# module_RevC.net
KiCad netlist of a schematic drawn in EAGLE
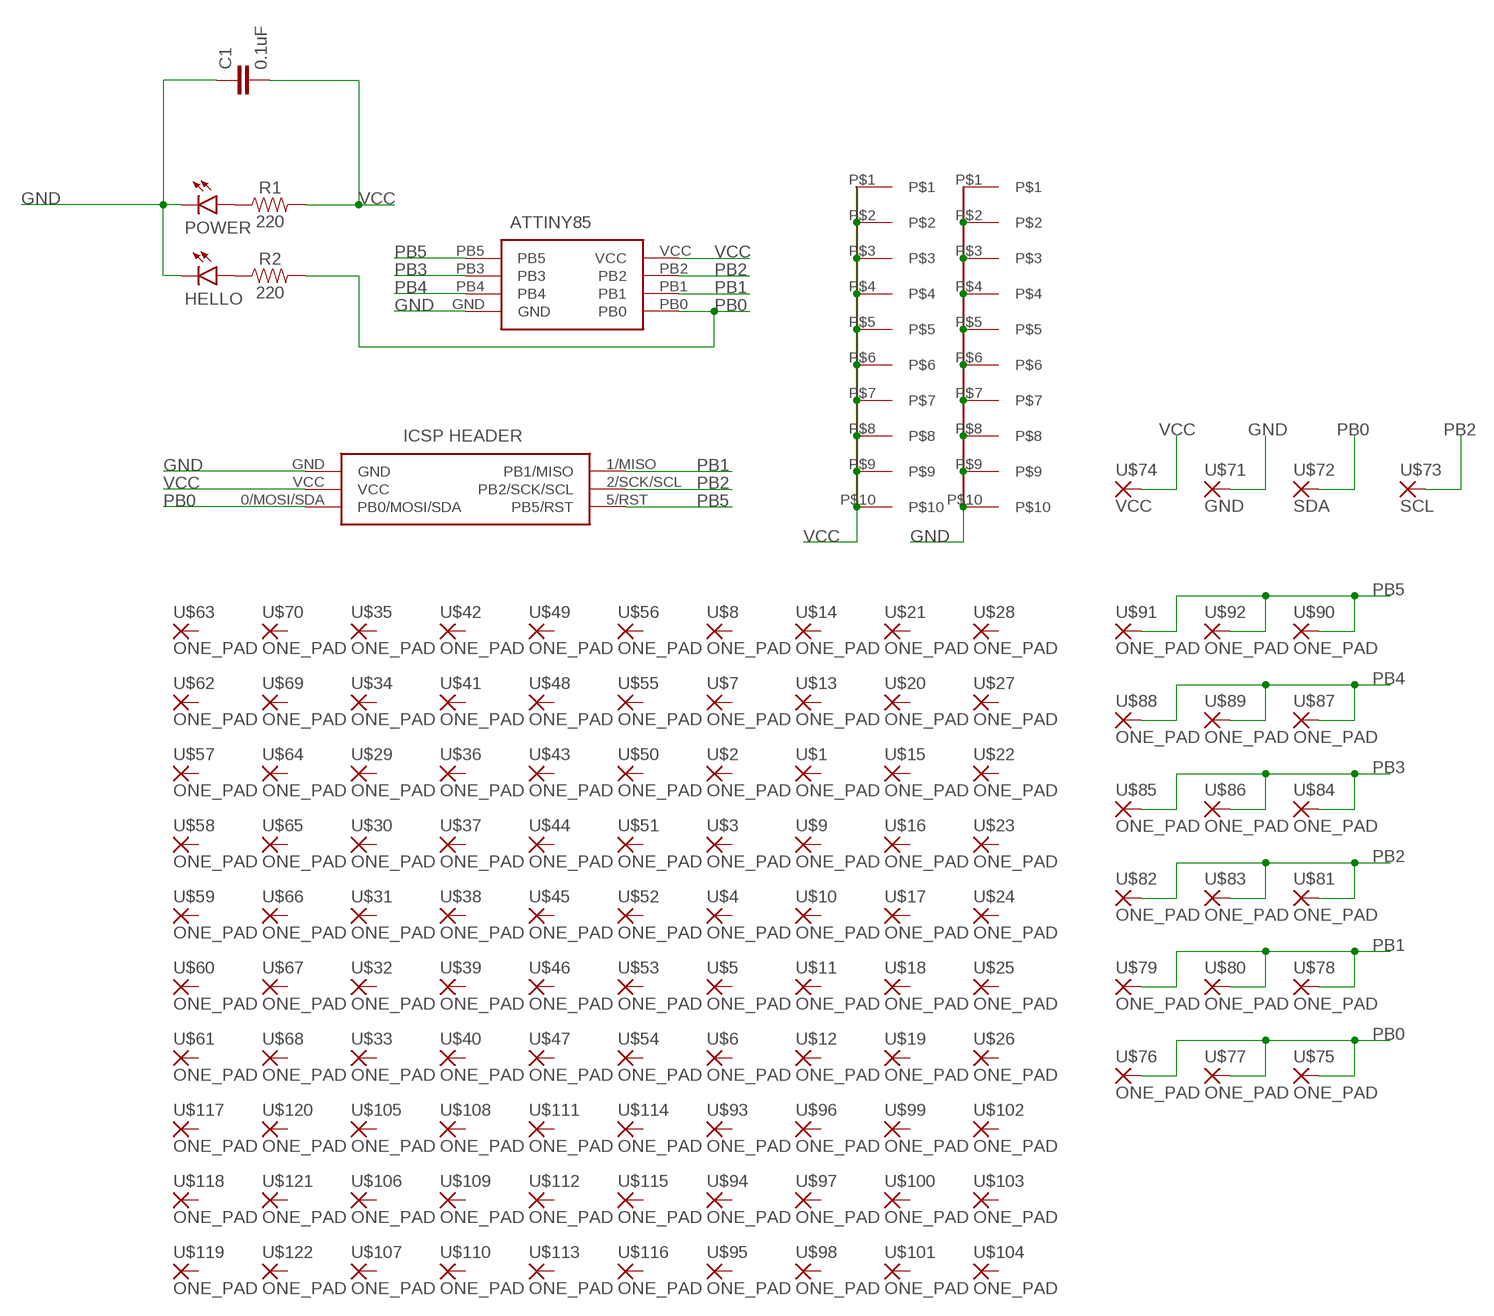
[diagram p0: schematic, sheet 1]

(export (version "E")
  (design (tool "Eeschema 10.0.6"))
  (components
    (comp (ref "C1")
      (value "0.1uF")
      (footprint "eagle-import:0603")
      (libsource (lib "eagle-import") (part "0.1UF-0603-25V-5%"))
    )
    (comp (ref "GND")
      (value "10X-PADS")
      (footprint "eagle-import:10X-PADS")
      (libsource (lib "eagle-import") (part "10X-PADS"))
    )
    (comp (ref "HELLO")
      (value "LED3MM")
      (footprint "eagle-import:LED3MM")
      (libsource (lib "eagle-import") (part "LED3MM"))
    )
    (comp (ref "IC1")
      (value "ATTINY85-20SU")
      (footprint "eagle-import:SOT127P798X216-8N")
      (fields (field (name "RS_PART_NUMBER") "1331674"))
      (libsource (lib "eagle-import") (part "ATTINY85-20SU"))
    )
    (comp (ref "J1")
      (value "M20-9980346")
      (footprint "eagle-import:HDRV6W64P254_2X3_762X508X868P")
      (fields (field (name "RS_PART_NUMBER") "7457046P"))
      (libsource (lib "eagle-import") (part "M20-9980346"))
    )
    (comp (ref "POWER")
      (value "LED3MM")
      (footprint "eagle-import:LED3MM")
      (libsource (lib "eagle-import") (part "LED3MM"))
    )
    (comp (ref "R1")
      (value "220")
      (footprint "eagle-import:AXIAL-0.3")
      (libsource (lib "eagle-import") (part "RESISTORAXIAL-0.3"))
    )
    (comp (ref "R2")
      (value "220")
      (footprint "eagle-import:AXIAL-0.3")
      (libsource (lib "eagle-import") (part "RESISTORAXIAL-0.3"))
    )
    (comp (ref "U$1")
      (value "ONE_PAD")
      (footprint "eagle-import:1X01")
      (libsource (lib "eagle-import") (part "ONE_PAD"))
    )
    (comp (ref "U$2")
      (value "ONE_PAD")
      (footprint "eagle-import:1X01")
      (libsource (lib "eagle-import") (part "ONE_PAD"))
    )
    (comp (ref "U$3")
      (value "ONE_PAD")
      (footprint "eagle-import:1X01")
      (libsource (lib "eagle-import") (part "ONE_PAD"))
    )
    (comp (ref "U$4")
      (value "ONE_PAD")
      (footprint "eagle-import:1X01")
      (libsource (lib "eagle-import") (part "ONE_PAD"))
    )
    (comp (ref "U$5")
      (value "ONE_PAD")
      (footprint "eagle-import:1X01")
      (libsource (lib "eagle-import") (part "ONE_PAD"))
    )
    (comp (ref "U$6")
      (value "ONE_PAD")
      (footprint "eagle-import:1X01")
      (libsource (lib "eagle-import") (part "ONE_PAD"))
    )
    (comp (ref "U$7")
      (value "ONE_PAD")
      (footprint "eagle-import:1X01")
      (libsource (lib "eagle-import") (part "ONE_PAD"))
    )
    (comp (ref "U$8")
      (value "ONE_PAD")
      (footprint "eagle-import:1X01")
      (libsource (lib "eagle-import") (part "ONE_PAD"))
    )
    (comp (ref "U$9")
      (value "ONE_PAD")
      (footprint "eagle-import:1X01")
      (libsource (lib "eagle-import") (part "ONE_PAD"))
    )
    (comp (ref "U$10")
      (value "ONE_PAD")
      (footprint "eagle-import:1X01")
      (libsource (lib "eagle-import") (part "ONE_PAD"))
    )
    (comp (ref "U$11")
      (value "ONE_PAD")
      (footprint "eagle-import:1X01")
      (libsource (lib "eagle-import") (part "ONE_PAD"))
    )
    (comp (ref "U$12")
      (value "ONE_PAD")
      (footprint "eagle-import:1X01")
      (libsource (lib "eagle-import") (part "ONE_PAD"))
    )
    (comp (ref "U$13")
      (value "ONE_PAD")
      (footprint "eagle-import:1X01")
      (libsource (lib "eagle-import") (part "ONE_PAD"))
    )
    (comp (ref "U$14")
      (value "ONE_PAD")
      (footprint "eagle-import:1X01")
      (libsource (lib "eagle-import") (part "ONE_PAD"))
    )
    (comp (ref "U$15")
      (value "ONE_PAD")
      (footprint "eagle-import:1X01")
      (libsource (lib "eagle-import") (part "ONE_PAD"))
    )
    (comp (ref "U$16")
      (value "ONE_PAD")
      (footprint "eagle-import:1X01")
      (libsource (lib "eagle-import") (part "ONE_PAD"))
    )
    (comp (ref "U$17")
      (value "ONE_PAD")
      (footprint "eagle-import:1X01")
      (libsource (lib "eagle-import") (part "ONE_PAD"))
    )
    (comp (ref "U$18")
      (value "ONE_PAD")
      (footprint "eagle-import:1X01")
      (libsource (lib "eagle-import") (part "ONE_PAD"))
    )
    (comp (ref "U$19")
      (value "ONE_PAD")
      (footprint "eagle-import:1X01")
      (libsource (lib "eagle-import") (part "ONE_PAD"))
    )
    (comp (ref "U$20")
      (value "ONE_PAD")
      (footprint "eagle-import:1X01")
      (libsource (lib "eagle-import") (part "ONE_PAD"))
    )
    (comp (ref "U$21")
      (value "ONE_PAD")
      (footprint "eagle-import:1X01")
      (libsource (lib "eagle-import") (part "ONE_PAD"))
    )
    (comp (ref "U$22")
      (value "ONE_PAD")
      (footprint "eagle-import:1X01")
      (libsource (lib "eagle-import") (part "ONE_PAD"))
    )
    (comp (ref "U$23")
      (value "ONE_PAD")
      (footprint "eagle-import:1X01")
      (libsource (lib "eagle-import") (part "ONE_PAD"))
    )
    (comp (ref "U$24")
      (value "ONE_PAD")
      (footprint "eagle-import:1X01")
      (libsource (lib "eagle-import") (part "ONE_PAD"))
    )
    (comp (ref "U$25")
      (value "ONE_PAD")
      (footprint "eagle-import:1X01")
      (libsource (lib "eagle-import") (part "ONE_PAD"))
    )
    (comp (ref "U$26")
      (value "ONE_PAD")
      (footprint "eagle-import:1X01")
      (libsource (lib "eagle-import") (part "ONE_PAD"))
    )
    (comp (ref "U$27")
      (value "ONE_PAD")
      (footprint "eagle-import:1X01")
      (libsource (lib "eagle-import") (part "ONE_PAD"))
    )
    (comp (ref "U$28")
      (value "ONE_PAD")
      (footprint "eagle-import:1X01")
      (libsource (lib "eagle-import") (part "ONE_PAD"))
    )
    (comp (ref "U$29")
      (value "ONE_PAD")
      (footprint "eagle-import:1X01")
      (libsource (lib "eagle-import") (part "ONE_PAD"))
    )
    (comp (ref "U$30")
      (value "ONE_PAD")
      (footprint "eagle-import:1X01")
      (libsource (lib "eagle-import") (part "ONE_PAD"))
    )
    (comp (ref "U$31")
      (value "ONE_PAD")
      (footprint "eagle-import:1X01")
      (libsource (lib "eagle-import") (part "ONE_PAD"))
    )
    (comp (ref "U$32")
      (value "ONE_PAD")
      (footprint "eagle-import:1X01")
      (libsource (lib "eagle-import") (part "ONE_PAD"))
    )
    (comp (ref "U$33")
      (value "ONE_PAD")
      (footprint "eagle-import:1X01")
      (libsource (lib "eagle-import") (part "ONE_PAD"))
    )
    (comp (ref "U$34")
      (value "ONE_PAD")
      (footprint "eagle-import:1X01")
      (libsource (lib "eagle-import") (part "ONE_PAD"))
    )
    (comp (ref "U$35")
      (value "ONE_PAD")
      (footprint "eagle-import:1X01")
      (libsource (lib "eagle-import") (part "ONE_PAD"))
    )
    (comp (ref "U$36")
      (value "ONE_PAD")
      (footprint "eagle-import:1X01")
      (libsource (lib "eagle-import") (part "ONE_PAD"))
    )
    (comp (ref "U$37")
      (value "ONE_PAD")
      (footprint "eagle-import:1X01")
      (libsource (lib "eagle-import") (part "ONE_PAD"))
    )
    (comp (ref "U$38")
      (value "ONE_PAD")
      (footprint "eagle-import:1X01")
      (libsource (lib "eagle-import") (part "ONE_PAD"))
    )
    (comp (ref "U$39")
      (value "ONE_PAD")
      (footprint "eagle-import:1X01")
      (libsource (lib "eagle-import") (part "ONE_PAD"))
    )
    (comp (ref "U$40")
      (value "ONE_PAD")
      (footprint "eagle-import:1X01")
      (libsource (lib "eagle-import") (part "ONE_PAD"))
    )
    (comp (ref "U$41")
      (value "ONE_PAD")
      (footprint "eagle-import:1X01")
      (libsource (lib "eagle-import") (part "ONE_PAD"))
    )
    (comp (ref "U$42")
      (value "ONE_PAD")
      (footprint "eagle-import:1X01")
      (libsource (lib "eagle-import") (part "ONE_PAD"))
    )
    (comp (ref "U$43")
      (value "ONE_PAD")
      (footprint "eagle-import:1X01")
      (libsource (lib "eagle-import") (part "ONE_PAD"))
    )
    (comp (ref "U$44")
      (value "ONE_PAD")
      (footprint "eagle-import:1X01")
      (libsource (lib "eagle-import") (part "ONE_PAD"))
    )
    (comp (ref "U$45")
      (value "ONE_PAD")
      (footprint "eagle-import:1X01")
      (libsource (lib "eagle-import") (part "ONE_PAD"))
    )
    (comp (ref "U$46")
      (value "ONE_PAD")
      (footprint "eagle-import:1X01")
      (libsource (lib "eagle-import") (part "ONE_PAD"))
    )
    (comp (ref "U$47")
      (value "ONE_PAD")
      (footprint "eagle-import:1X01")
      (libsource (lib "eagle-import") (part "ONE_PAD"))
    )
    (comp (ref "U$48")
      (value "ONE_PAD")
      (footprint "eagle-import:1X01")
      (libsource (lib "eagle-import") (part "ONE_PAD"))
    )
    (comp (ref "U$49")
      (value "ONE_PAD")
      (footprint "eagle-import:1X01")
      (libsource (lib "eagle-import") (part "ONE_PAD"))
    )
    (comp (ref "U$50")
      (value "ONE_PAD")
      (footprint "eagle-import:1X01")
      (libsource (lib "eagle-import") (part "ONE_PAD"))
    )
    (comp (ref "U$51")
      (value "ONE_PAD")
      (footprint "eagle-import:1X01")
      (libsource (lib "eagle-import") (part "ONE_PAD"))
    )
    (comp (ref "U$52")
      (value "ONE_PAD")
      (footprint "eagle-import:1X01")
      (libsource (lib "eagle-import") (part "ONE_PAD"))
    )
    (comp (ref "U$53")
      (value "ONE_PAD")
      (footprint "eagle-import:1X01")
      (libsource (lib "eagle-import") (part "ONE_PAD"))
    )
    (comp (ref "U$54")
      (value "ONE_PAD")
      (footprint "eagle-import:1X01")
      (libsource (lib "eagle-import") (part "ONE_PAD"))
    )
    (comp (ref "U$55")
      (value "ONE_PAD")
      (footprint "eagle-import:1X01")
      (libsource (lib "eagle-import") (part "ONE_PAD"))
    )
    (comp (ref "U$56")
      (value "ONE_PAD")
      (footprint "eagle-import:1X01")
      (libsource (lib "eagle-import") (part "ONE_PAD"))
    )
    (comp (ref "U$57")
      (value "ONE_PAD")
      (footprint "eagle-import:1X01")
      (libsource (lib "eagle-import") (part "ONE_PAD"))
    )
    (comp (ref "U$58")
      (value "ONE_PAD")
      (footprint "eagle-import:1X01")
      (libsource (lib "eagle-import") (part "ONE_PAD"))
    )
    (comp (ref "U$59")
      (value "ONE_PAD")
      (footprint "eagle-import:1X01")
      (libsource (lib "eagle-import") (part "ONE_PAD"))
    )
    (comp (ref "U$60")
      (value "ONE_PAD")
      (footprint "eagle-import:1X01")
      (libsource (lib "eagle-import") (part "ONE_PAD"))
    )
    (comp (ref "U$61")
      (value "ONE_PAD")
      (footprint "eagle-import:1X01")
      (libsource (lib "eagle-import") (part "ONE_PAD"))
    )
    (comp (ref "U$62")
      (value "ONE_PAD")
      (footprint "eagle-import:1X01")
      (libsource (lib "eagle-import") (part "ONE_PAD"))
    )
    (comp (ref "U$63")
      (value "ONE_PAD")
      (footprint "eagle-import:1X01")
      (libsource (lib "eagle-import") (part "ONE_PAD"))
    )
    (comp (ref "U$64")
      (value "ONE_PAD")
      (footprint "eagle-import:1X01")
      (libsource (lib "eagle-import") (part "ONE_PAD"))
    )
    (comp (ref "U$65")
      (value "ONE_PAD")
      (footprint "eagle-import:1X01")
      (libsource (lib "eagle-import") (part "ONE_PAD"))
    )
    (comp (ref "U$66")
      (value "ONE_PAD")
      (footprint "eagle-import:1X01")
      (libsource (lib "eagle-import") (part "ONE_PAD"))
    )
    (comp (ref "U$67")
      (value "ONE_PAD")
      (footprint "eagle-import:1X01")
      (libsource (lib "eagle-import") (part "ONE_PAD"))
    )
    (comp (ref "U$68")
      (value "ONE_PAD")
      (footprint "eagle-import:1X01")
      (libsource (lib "eagle-import") (part "ONE_PAD"))
    )
    (comp (ref "U$69")
      (value "ONE_PAD")
      (footprint "eagle-import:1X01")
      (libsource (lib "eagle-import") (part "ONE_PAD"))
    )
    (comp (ref "U$70")
      (value "ONE_PAD")
      (footprint "eagle-import:1X01")
      (libsource (lib "eagle-import") (part "ONE_PAD"))
    )
    (comp (ref "U$71")
      (value "GND")
      (footprint "eagle-import:1X01")
      (libsource (lib "eagle-import") (part "ONE_PAD"))
    )
    (comp (ref "U$72")
      (value "SDA")
      (footprint "eagle-import:1X01")
      (libsource (lib "eagle-import") (part "ONE_PAD"))
    )
    (comp (ref "U$73")
      (value "SCL")
      (footprint "eagle-import:1X01")
      (libsource (lib "eagle-import") (part "ONE_PAD"))
    )
    (comp (ref "U$74")
      (value "VCC")
      (footprint "eagle-import:1X01")
      (libsource (lib "eagle-import") (part "ONE_PAD"))
    )
    (comp (ref "U$75")
      (value "ONE_PAD")
      (footprint "eagle-import:1X01")
      (libsource (lib "eagle-import") (part "ONE_PAD"))
    )
    (comp (ref "U$76")
      (value "ONE_PAD")
      (footprint "eagle-import:1X01")
      (libsource (lib "eagle-import") (part "ONE_PAD"))
    )
    (comp (ref "U$77")
      (value "ONE_PAD")
      (footprint "eagle-import:1X01")
      (libsource (lib "eagle-import") (part "ONE_PAD"))
    )
    (comp (ref "U$78")
      (value "ONE_PAD")
      (footprint "eagle-import:1X01")
      (libsource (lib "eagle-import") (part "ONE_PAD"))
    )
    (comp (ref "U$79")
      (value "ONE_PAD")
      (footprint "eagle-import:1X01")
      (libsource (lib "eagle-import") (part "ONE_PAD"))
    )
    (comp (ref "U$80")
      (value "ONE_PAD")
      (footprint "eagle-import:1X01")
      (libsource (lib "eagle-import") (part "ONE_PAD"))
    )
    (comp (ref "U$81")
      (value "ONE_PAD")
      (footprint "eagle-import:1X01")
      (libsource (lib "eagle-import") (part "ONE_PAD"))
    )
    (comp (ref "U$82")
      (value "ONE_PAD")
      (footprint "eagle-import:1X01")
      (libsource (lib "eagle-import") (part "ONE_PAD"))
    )
    (comp (ref "U$83")
      (value "ONE_PAD")
      (footprint "eagle-import:1X01")
      (libsource (lib "eagle-import") (part "ONE_PAD"))
    )
    (comp (ref "U$84")
      (value "ONE_PAD")
      (footprint "eagle-import:1X01")
      (libsource (lib "eagle-import") (part "ONE_PAD"))
    )
    (comp (ref "U$85")
      (value "ONE_PAD")
      (footprint "eagle-import:1X01")
      (libsource (lib "eagle-import") (part "ONE_PAD"))
    )
    (comp (ref "U$86")
      (value "ONE_PAD")
      (footprint "eagle-import:1X01")
      (libsource (lib "eagle-import") (part "ONE_PAD"))
    )
    (comp (ref "U$87")
      (value "ONE_PAD")
      (footprint "eagle-import:1X01")
      (libsource (lib "eagle-import") (part "ONE_PAD"))
    )
    (comp (ref "U$88")
      (value "ONE_PAD")
      (footprint "eagle-import:1X01")
      (libsource (lib "eagle-import") (part "ONE_PAD"))
    )
    (comp (ref "U$89")
      (value "ONE_PAD")
      (footprint "eagle-import:1X01")
      (libsource (lib "eagle-import") (part "ONE_PAD"))
    )
    (comp (ref "U$90")
      (value "ONE_PAD")
      (footprint "eagle-import:1X01")
      (libsource (lib "eagle-import") (part "ONE_PAD"))
    )
    (comp (ref "U$91")
      (value "ONE_PAD")
      (footprint "eagle-import:1X01")
      (libsource (lib "eagle-import") (part "ONE_PAD"))
    )
    (comp (ref "U$92")
      (value "ONE_PAD")
      (footprint "eagle-import:1X01")
      (libsource (lib "eagle-import") (part "ONE_PAD"))
    )
    (comp (ref "U$93")
      (value "ONE_PAD")
      (footprint "eagle-import:1X01")
      (libsource (lib "eagle-import") (part "ONE_PAD"))
    )
    (comp (ref "U$94")
      (value "ONE_PAD")
      (footprint "eagle-import:1X01")
      (libsource (lib "eagle-import") (part "ONE_PAD"))
    )
    (comp (ref "U$95")
      (value "ONE_PAD")
      (footprint "eagle-import:1X01")
      (libsource (lib "eagle-import") (part "ONE_PAD"))
    )
    (comp (ref "U$96")
      (value "ONE_PAD")
      (footprint "eagle-import:1X01")
      (libsource (lib "eagle-import") (part "ONE_PAD"))
    )
    (comp (ref "U$97")
      (value "ONE_PAD")
      (footprint "eagle-import:1X01")
      (libsource (lib "eagle-import") (part "ONE_PAD"))
    )
    (comp (ref "U$98")
      (value "ONE_PAD")
      (footprint "eagle-import:1X01")
      (libsource (lib "eagle-import") (part "ONE_PAD"))
    )
    (comp (ref "U$99")
      (value "ONE_PAD")
      (footprint "eagle-import:1X01")
      (libsource (lib "eagle-import") (part "ONE_PAD"))
    )
    (comp (ref "U$100")
      (value "ONE_PAD")
      (footprint "eagle-import:1X01")
      (libsource (lib "eagle-import") (part "ONE_PAD"))
    )
    (comp (ref "U$101")
      (value "ONE_PAD")
      (footprint "eagle-import:1X01")
      (libsource (lib "eagle-import") (part "ONE_PAD"))
    )
    (comp (ref "U$102")
      (value "ONE_PAD")
      (footprint "eagle-import:1X01")
      (libsource (lib "eagle-import") (part "ONE_PAD"))
    )
    (comp (ref "U$103")
      (value "ONE_PAD")
      (footprint "eagle-import:1X01")
      (libsource (lib "eagle-import") (part "ONE_PAD"))
    )
    (comp (ref "U$104")
      (value "ONE_PAD")
      (footprint "eagle-import:1X01")
      (libsource (lib "eagle-import") (part "ONE_PAD"))
    )
    (comp (ref "U$105")
      (value "ONE_PAD")
      (footprint "eagle-import:1X01")
      (libsource (lib "eagle-import") (part "ONE_PAD"))
    )
    (comp (ref "U$106")
      (value "ONE_PAD")
      (footprint "eagle-import:1X01")
      (libsource (lib "eagle-import") (part "ONE_PAD"))
    )
    (comp (ref "U$107")
      (value "ONE_PAD")
      (footprint "eagle-import:1X01")
      (libsource (lib "eagle-import") (part "ONE_PAD"))
    )
    (comp (ref "U$108")
      (value "ONE_PAD")
      (footprint "eagle-import:1X01")
      (libsource (lib "eagle-import") (part "ONE_PAD"))
    )
    (comp (ref "U$109")
      (value "ONE_PAD")
      (footprint "eagle-import:1X01")
      (libsource (lib "eagle-import") (part "ONE_PAD"))
    )
    (comp (ref "U$110")
      (value "ONE_PAD")
      (footprint "eagle-import:1X01")
      (libsource (lib "eagle-import") (part "ONE_PAD"))
    )
    (comp (ref "U$111")
      (value "ONE_PAD")
      (footprint "eagle-import:1X01")
      (libsource (lib "eagle-import") (part "ONE_PAD"))
    )
    (comp (ref "U$112")
      (value "ONE_PAD")
      (footprint "eagle-import:1X01")
      (libsource (lib "eagle-import") (part "ONE_PAD"))
    )
    (comp (ref "U$113")
      (value "ONE_PAD")
      (footprint "eagle-import:1X01")
      (libsource (lib "eagle-import") (part "ONE_PAD"))
    )
    (comp (ref "U$114")
      (value "ONE_PAD")
      (footprint "eagle-import:1X01")
      (libsource (lib "eagle-import") (part "ONE_PAD"))
    )
    (comp (ref "U$115")
      (value "ONE_PAD")
      (footprint "eagle-import:1X01")
      (libsource (lib "eagle-import") (part "ONE_PAD"))
    )
    (comp (ref "U$116")
      (value "ONE_PAD")
      (footprint "eagle-import:1X01")
      (libsource (lib "eagle-import") (part "ONE_PAD"))
    )
    (comp (ref "U$117")
      (value "ONE_PAD")
      (footprint "eagle-import:1X01")
      (libsource (lib "eagle-import") (part "ONE_PAD"))
    )
    (comp (ref "U$118")
      (value "ONE_PAD")
      (footprint "eagle-import:1X01")
      (libsource (lib "eagle-import") (part "ONE_PAD"))
    )
    (comp (ref "U$119")
      (value "ONE_PAD")
      (footprint "eagle-import:1X01")
      (libsource (lib "eagle-import") (part "ONE_PAD"))
    )
    (comp (ref "U$120")
      (value "ONE_PAD")
      (footprint "eagle-import:1X01")
      (libsource (lib "eagle-import") (part "ONE_PAD"))
    )
    (comp (ref "U$121")
      (value "ONE_PAD")
      (footprint "eagle-import:1X01")
      (libsource (lib "eagle-import") (part "ONE_PAD"))
    )
    (comp (ref "U$122")
      (value "ONE_PAD")
      (footprint "eagle-import:1X01")
      (libsource (lib "eagle-import") (part "ONE_PAD"))
    )
    (comp (ref "VCC")
      (value "10X-PADS")
      (footprint "eagle-import:10X-PADS")
      (libsource (lib "eagle-import") (part "10X-PADS"))
    )
  )
  (nets
    (net (code "1") (name "/GND") (class "Default")
      (node (ref "C1") (pin "1") (pinfunction "1_1") (pintype "passive"))
      (node (ref "GND") (pin "P$1") (pinfunction "P$1_P$1") (pintype "bidirectional"))
      (node (ref "GND") (pin "P$10") (pinfunction "P$10_P$10") (pintype "bidirectional"))
      (node (ref "GND") (pin "P$2") (pinfunction "P$2_P$2") (pintype "bidirectional"))
      (node (ref "GND") (pin "P$3") (pinfunction "P$3_P$3") (pintype "bidirectional"))
      (node (ref "GND") (pin "P$4") (pinfunction "P$4_P$4") (pintype "bidirectional"))
      (node (ref "GND") (pin "P$5") (pinfunction "P$5_P$5") (pintype "bidirectional"))
      (node (ref "GND") (pin "P$6") (pinfunction "P$6_P$6") (pintype "bidirectional"))
      (node (ref "GND") (pin "P$7") (pinfunction "P$7_P$7") (pintype "bidirectional"))
      (node (ref "GND") (pin "P$8") (pinfunction "P$8_P$8") (pintype "bidirectional"))
      (node (ref "GND") (pin "P$9") (pinfunction "P$9_P$9") (pintype "bidirectional"))
      (node (ref "HELLO") (pin "NEG") (pinfunction "NEG_NEG") (pintype "passive"))
      (node (ref "IC1") (pin "GND") (pinfunction "GND_GND") (pintype "bidirectional"))
      (node (ref "J1") (pin "GND") (pinfunction "GND_GND") (pintype "bidirectional"))
      (node (ref "POWER") (pin "NEG") (pinfunction "NEG_NEG") (pintype "passive"))
      (node (ref "U$71") (pin "1") (pinfunction "P_1") (pintype "passive"))
    )
    (net (code "2") (name "/PB0") (class "Default")
      (node (ref "IC1") (pin "PB0") (pinfunction "PB0_PB0") (pintype "bidirectional"))
      (node (ref "J1") (pin "0/MOSI/SDA") (pinfunction "PB0/MOSI/SDA_0/MOSI/SDA") (pintype "bidirectional"))
      (node (ref "R2") (pin "P$2") (pinfunction "2_P$2") (pintype "passive"))
      (node (ref "U$72") (pin "1") (pinfunction "P_1") (pintype "passive"))
      (node (ref "U$75") (pin "1") (pinfunction "P_1") (pintype "passive"))
      (node (ref "U$76") (pin "1") (pinfunction "P_1") (pintype "passive"))
      (node (ref "U$77") (pin "1") (pinfunction "P_1") (pintype "passive"))
    )
    (net (code "3") (name "/PB1") (class "Default")
      (node (ref "IC1") (pin "PB1") (pinfunction "PB1_PB1") (pintype "bidirectional"))
      (node (ref "J1") (pin "1/MISO") (pinfunction "PB1/MISO_1/MISO") (pintype "bidirectional"))
      (node (ref "U$78") (pin "1") (pinfunction "P_1") (pintype "passive"))
      (node (ref "U$79") (pin "1") (pinfunction "P_1") (pintype "passive"))
      (node (ref "U$80") (pin "1") (pinfunction "P_1") (pintype "passive"))
    )
    (net (code "4") (name "/PB2") (class "Default")
      (node (ref "IC1") (pin "PB2") (pinfunction "PB2_PB2") (pintype "bidirectional"))
      (node (ref "J1") (pin "2/SCK/SCL") (pinfunction "PB2/SCK/SCL_2/SCK/SCL") (pintype "bidirectional"))
      (node (ref "U$73") (pin "1") (pinfunction "P_1") (pintype "passive"))
      (node (ref "U$81") (pin "1") (pinfunction "P_1") (pintype "passive"))
      (node (ref "U$82") (pin "1") (pinfunction "P_1") (pintype "passive"))
      (node (ref "U$83") (pin "1") (pinfunction "P_1") (pintype "passive"))
    )
    (net (code "5") (name "/PB3") (class "Default")
      (node (ref "IC1") (pin "PB3") (pinfunction "PB3_PB3") (pintype "bidirectional"))
      (node (ref "U$84") (pin "1") (pinfunction "P_1") (pintype "passive"))
      (node (ref "U$85") (pin "1") (pinfunction "P_1") (pintype "passive"))
      (node (ref "U$86") (pin "1") (pinfunction "P_1") (pintype "passive"))
    )
    (net (code "6") (name "/PB4") (class "Default")
      (node (ref "IC1") (pin "PB4") (pinfunction "PB4_PB4") (pintype "bidirectional"))
      (node (ref "U$87") (pin "1") (pinfunction "P_1") (pintype "passive"))
      (node (ref "U$88") (pin "1") (pinfunction "P_1") (pintype "passive"))
      (node (ref "U$89") (pin "1") (pinfunction "P_1") (pintype "passive"))
    )
    (net (code "7") (name "/PB5") (class "Default")
      (node (ref "IC1") (pin "PB5") (pinfunction "PB5_PB5") (pintype "bidirectional"))
      (node (ref "J1") (pin "5/RST") (pinfunction "PB5/RST_5/RST") (pintype "bidirectional"))
      (node (ref "U$90") (pin "1") (pinfunction "P_1") (pintype "passive"))
      (node (ref "U$91") (pin "1") (pinfunction "P_1") (pintype "passive"))
      (node (ref "U$92") (pin "1") (pinfunction "P_1") (pintype "passive"))
    )
    (net (code "8") (name "/VCC") (class "Default")
      (node (ref "C1") (pin "2") (pinfunction "2_2") (pintype "passive"))
      (node (ref "IC1") (pin "VCC") (pinfunction "VCC_VCC") (pintype "bidirectional"))
      (node (ref "J1") (pin "VCC") (pinfunction "VCC_VCC") (pintype "bidirectional"))
      (node (ref "R1") (pin "P$2") (pinfunction "2_P$2") (pintype "passive"))
      (node (ref "U$74") (pin "1") (pinfunction "P_1") (pintype "passive"))
      (node (ref "VCC") (pin "P$1") (pinfunction "P$1_P$1") (pintype "bidirectional"))
      (node (ref "VCC") (pin "P$10") (pinfunction "P$10_P$10") (pintype "bidirectional"))
      (node (ref "VCC") (pin "P$2") (pinfunction "P$2_P$2") (pintype "bidirectional"))
      (node (ref "VCC") (pin "P$3") (pinfunction "P$3_P$3") (pintype "bidirectional"))
      (node (ref "VCC") (pin "P$4") (pinfunction "P$4_P$4") (pintype "bidirectional"))
      (node (ref "VCC") (pin "P$5") (pinfunction "P$5_P$5") (pintype "bidirectional"))
      (node (ref "VCC") (pin "P$6") (pinfunction "P$6_P$6") (pintype "bidirectional"))
      (node (ref "VCC") (pin "P$7") (pinfunction "P$7_P$7") (pintype "bidirectional"))
      (node (ref "VCC") (pin "P$8") (pinfunction "P$8_P$8") (pintype "bidirectional"))
      (node (ref "VCC") (pin "P$9") (pinfunction "P$9_P$9") (pintype "bidirectional"))
    )
    (net (code "9") (name "Net-(R1-1)") (class "Default")
      (node (ref "POWER") (pin "POS") (pinfunction "POS_POS") (pintype "passive"))
      (node (ref "R1") (pin "P$1") (pinfunction "1_P$1") (pintype "passive"))
    )
    (net (code "10") (name "Net-(R2-1)") (class "Default")
      (node (ref "HELLO") (pin "POS") (pinfunction "POS_POS") (pintype "passive"))
      (node (ref "R2") (pin "P$1") (pinfunction "1_P$1") (pintype "passive"))
    )
    (net (code "11") (name "unconnected-(U$1-P-Pad1)") (class "Default")
      (node (ref "U$1") (pin "1") (pinfunction "P_1") (pintype "passive"))
    )
    (net (code "12") (name "unconnected-(U$2-P-Pad1)") (class "Default")
      (node (ref "U$2") (pin "1") (pinfunction "P_1") (pintype "passive"))
    )
    (net (code "13") (name "unconnected-(U$3-P-Pad1)") (class "Default")
      (node (ref "U$3") (pin "1") (pinfunction "P_1") (pintype "passive"))
    )
    (net (code "14") (name "unconnected-(U$4-P-Pad1)") (class "Default")
      (node (ref "U$4") (pin "1") (pinfunction "P_1") (pintype "passive"))
    )
    (net (code "15") (name "unconnected-(U$5-P-Pad1)") (class "Default")
      (node (ref "U$5") (pin "1") (pinfunction "P_1") (pintype "passive"))
    )
    (net (code "16") (name "unconnected-(U$6-P-Pad1)") (class "Default")
      (node (ref "U$6") (pin "1") (pinfunction "P_1") (pintype "passive"))
    )
    (net (code "17") (name "unconnected-(U$7-P-Pad1)") (class "Default")
      (node (ref "U$7") (pin "1") (pinfunction "P_1") (pintype "passive"))
    )
    (net (code "18") (name "unconnected-(U$8-P-Pad1)") (class "Default")
      (node (ref "U$8") (pin "1") (pinfunction "P_1") (pintype "passive"))
    )
    (net (code "19") (name "unconnected-(U$9-P-Pad1)") (class "Default")
      (node (ref "U$9") (pin "1") (pinfunction "P_1") (pintype "passive"))
    )
    (net (code "20") (name "unconnected-(U$10-P-Pad1)") (class "Default")
      (node (ref "U$10") (pin "1") (pinfunction "P_1") (pintype "passive"))
    )
    (net (code "21") (name "unconnected-(U$11-P-Pad1)") (class "Default")
      (node (ref "U$11") (pin "1") (pinfunction "P_1") (pintype "passive"))
    )
    (net (code "22") (name "unconnected-(U$12-P-Pad1)") (class "Default")
      (node (ref "U$12") (pin "1") (pinfunction "P_1") (pintype "passive"))
    )
    (net (code "23") (name "unconnected-(U$13-P-Pad1)") (class "Default")
      (node (ref "U$13") (pin "1") (pinfunction "P_1") (pintype "passive"))
    )
    (net (code "24") (name "unconnected-(U$14-P-Pad1)") (class "Default")
      (node (ref "U$14") (pin "1") (pinfunction "P_1") (pintype "passive"))
    )
    (net (code "25") (name "unconnected-(U$15-P-Pad1)") (class "Default")
      (node (ref "U$15") (pin "1") (pinfunction "P_1") (pintype "passive"))
    )
    (net (code "26") (name "unconnected-(U$16-P-Pad1)") (class "Default")
      (node (ref "U$16") (pin "1") (pinfunction "P_1") (pintype "passive"))
    )
    (net (code "27") (name "unconnected-(U$17-P-Pad1)") (class "Default")
      (node (ref "U$17") (pin "1") (pinfunction "P_1") (pintype "passive"))
    )
    (net (code "28") (name "unconnected-(U$18-P-Pad1)") (class "Default")
      (node (ref "U$18") (pin "1") (pinfunction "P_1") (pintype "passive"))
    )
    (net (code "29") (name "unconnected-(U$19-P-Pad1)") (class "Default")
      (node (ref "U$19") (pin "1") (pinfunction "P_1") (pintype "passive"))
    )
    (net (code "30") (name "unconnected-(U$20-P-Pad1)") (class "Default")
      (node (ref "U$20") (pin "1") (pinfunction "P_1") (pintype "passive"))
    )
    (net (code "31") (name "unconnected-(U$21-P-Pad1)") (class "Default")
      (node (ref "U$21") (pin "1") (pinfunction "P_1") (pintype "passive"))
    )
    (net (code "32") (name "unconnected-(U$22-P-Pad1)") (class "Default")
      (node (ref "U$22") (pin "1") (pinfunction "P_1") (pintype "passive"))
    )
    (net (code "33") (name "unconnected-(U$23-P-Pad1)") (class "Default")
      (node (ref "U$23") (pin "1") (pinfunction "P_1") (pintype "passive"))
    )
    (net (code "34") (name "unconnected-(U$24-P-Pad1)") (class "Default")
      (node (ref "U$24") (pin "1") (pinfunction "P_1") (pintype "passive"))
    )
    (net (code "35") (name "unconnected-(U$25-P-Pad1)") (class "Default")
      (node (ref "U$25") (pin "1") (pinfunction "P_1") (pintype "passive"))
    )
    (net (code "36") (name "unconnected-(U$26-P-Pad1)") (class "Default")
      (node (ref "U$26") (pin "1") (pinfunction "P_1") (pintype "passive"))
    )
    (net (code "37") (name "unconnected-(U$27-P-Pad1)") (class "Default")
      (node (ref "U$27") (pin "1") (pinfunction "P_1") (pintype "passive"))
    )
    (net (code "38") (name "unconnected-(U$28-P-Pad1)") (class "Default")
      (node (ref "U$28") (pin "1") (pinfunction "P_1") (pintype "passive"))
    )
    (net (code "39") (name "unconnected-(U$29-P-Pad1)") (class "Default")
      (node (ref "U$29") (pin "1") (pinfunction "P_1") (pintype "passive"))
    )
    (net (code "40") (name "unconnected-(U$30-P-Pad1)") (class "Default")
      (node (ref "U$30") (pin "1") (pinfunction "P_1") (pintype "passive"))
    )
    (net (code "41") (name "unconnected-(U$31-P-Pad1)") (class "Default")
      (node (ref "U$31") (pin "1") (pinfunction "P_1") (pintype "passive"))
    )
    (net (code "42") (name "unconnected-(U$32-P-Pad1)") (class "Default")
      (node (ref "U$32") (pin "1") (pinfunction "P_1") (pintype "passive"))
    )
    (net (code "43") (name "unconnected-(U$33-P-Pad1)") (class "Default")
      (node (ref "U$33") (pin "1") (pinfunction "P_1") (pintype "passive"))
    )
    (net (code "44") (name "unconnected-(U$34-P-Pad1)") (class "Default")
      (node (ref "U$34") (pin "1") (pinfunction "P_1") (pintype "passive"))
    )
    (net (code "45") (name "unconnected-(U$35-P-Pad1)") (class "Default")
      (node (ref "U$35") (pin "1") (pinfunction "P_1") (pintype "passive"))
    )
    (net (code "46") (name "unconnected-(U$36-P-Pad1)") (class "Default")
      (node (ref "U$36") (pin "1") (pinfunction "P_1") (pintype "passive"))
    )
    (net (code "47") (name "unconnected-(U$37-P-Pad1)") (class "Default")
      (node (ref "U$37") (pin "1") (pinfunction "P_1") (pintype "passive"))
    )
    (net (code "48") (name "unconnected-(U$38-P-Pad1)") (class "Default")
      (node (ref "U$38") (pin "1") (pinfunction "P_1") (pintype "passive"))
    )
    (net (code "49") (name "unconnected-(U$39-P-Pad1)") (class "Default")
      (node (ref "U$39") (pin "1") (pinfunction "P_1") (pintype "passive"))
    )
    (net (code "50") (name "unconnected-(U$40-P-Pad1)") (class "Default")
      (node (ref "U$40") (pin "1") (pinfunction "P_1") (pintype "passive"))
    )
    (net (code "51") (name "unconnected-(U$41-P-Pad1)") (class "Default")
      (node (ref "U$41") (pin "1") (pinfunction "P_1") (pintype "passive"))
    )
    (net (code "52") (name "unconnected-(U$42-P-Pad1)") (class "Default")
      (node (ref "U$42") (pin "1") (pinfunction "P_1") (pintype "passive"))
    )
    (net (code "53") (name "unconnected-(U$43-P-Pad1)") (class "Default")
      (node (ref "U$43") (pin "1") (pinfunction "P_1") (pintype "passive"))
    )
    (net (code "54") (name "unconnected-(U$44-P-Pad1)") (class "Default")
      (node (ref "U$44") (pin "1") (pinfunction "P_1") (pintype "passive"))
    )
    (net (code "55") (name "unconnected-(U$45-P-Pad1)") (class "Default")
      (node (ref "U$45") (pin "1") (pinfunction "P_1") (pintype "passive"))
    )
    (net (code "56") (name "unconnected-(U$46-P-Pad1)") (class "Default")
      (node (ref "U$46") (pin "1") (pinfunction "P_1") (pintype "passive"))
    )
    (net (code "57") (name "unconnected-(U$47-P-Pad1)") (class "Default")
      (node (ref "U$47") (pin "1") (pinfunction "P_1") (pintype "passive"))
    )
    (net (code "58") (name "unconnected-(U$48-P-Pad1)") (class "Default")
      (node (ref "U$48") (pin "1") (pinfunction "P_1") (pintype "passive"))
    )
    (net (code "59") (name "unconnected-(U$49-P-Pad1)") (class "Default")
      (node (ref "U$49") (pin "1") (pinfunction "P_1") (pintype "passive"))
    )
    (net (code "60") (name "unconnected-(U$50-P-Pad1)") (class "Default")
      (node (ref "U$50") (pin "1") (pinfunction "P_1") (pintype "passive"))
    )
    (net (code "61") (name "unconnected-(U$51-P-Pad1)") (class "Default")
      (node (ref "U$51") (pin "1") (pinfunction "P_1") (pintype "passive"))
    )
    (net (code "62") (name "unconnected-(U$52-P-Pad1)") (class "Default")
      (node (ref "U$52") (pin "1") (pinfunction "P_1") (pintype "passive"))
    )
    (net (code "63") (name "unconnected-(U$53-P-Pad1)") (class "Default")
      (node (ref "U$53") (pin "1") (pinfunction "P_1") (pintype "passive"))
    )
    (net (code "64") (name "unconnected-(U$54-P-Pad1)") (class "Default")
      (node (ref "U$54") (pin "1") (pinfunction "P_1") (pintype "passive"))
    )
    (net (code "65") (name "unconnected-(U$55-P-Pad1)") (class "Default")
      (node (ref "U$55") (pin "1") (pinfunction "P_1") (pintype "passive"))
    )
    (net (code "66") (name "unconnected-(U$56-P-Pad1)") (class "Default")
      (node (ref "U$56") (pin "1") (pinfunction "P_1") (pintype "passive"))
    )
    (net (code "67") (name "unconnected-(U$57-P-Pad1)") (class "Default")
      (node (ref "U$57") (pin "1") (pinfunction "P_1") (pintype "passive"))
    )
    (net (code "68") (name "unconnected-(U$58-P-Pad1)") (class "Default")
      (node (ref "U$58") (pin "1") (pinfunction "P_1") (pintype "passive"))
    )
    (net (code "69") (name "unconnected-(U$59-P-Pad1)") (class "Default")
      (node (ref "U$59") (pin "1") (pinfunction "P_1") (pintype "passive"))
    )
    (net (code "70") (name "unconnected-(U$60-P-Pad1)") (class "Default")
      (node (ref "U$60") (pin "1") (pinfunction "P_1") (pintype "passive"))
    )
    (net (code "71") (name "unconnected-(U$61-P-Pad1)") (class "Default")
      (node (ref "U$61") (pin "1") (pinfunction "P_1") (pintype "passive"))
    )
    (net (code "72") (name "unconnected-(U$62-P-Pad1)") (class "Default")
      (node (ref "U$62") (pin "1") (pinfunction "P_1") (pintype "passive"))
    )
    (net (code "73") (name "unconnected-(U$63-P-Pad1)") (class "Default")
      (node (ref "U$63") (pin "1") (pinfunction "P_1") (pintype "passive"))
    )
    (net (code "74") (name "unconnected-(U$64-P-Pad1)") (class "Default")
      (node (ref "U$64") (pin "1") (pinfunction "P_1") (pintype "passive"))
    )
    (net (code "75") (name "unconnected-(U$65-P-Pad1)") (class "Default")
      (node (ref "U$65") (pin "1") (pinfunction "P_1") (pintype "passive"))
    )
    (net (code "76") (name "unconnected-(U$66-P-Pad1)") (class "Default")
      (node (ref "U$66") (pin "1") (pinfunction "P_1") (pintype "passive"))
    )
    (net (code "77") (name "unconnected-(U$67-P-Pad1)") (class "Default")
      (node (ref "U$67") (pin "1") (pinfunction "P_1") (pintype "passive"))
    )
    (net (code "78") (name "unconnected-(U$68-P-Pad1)") (class "Default")
      (node (ref "U$68") (pin "1") (pinfunction "P_1") (pintype "passive"))
    )
    (net (code "79") (name "unconnected-(U$69-P-Pad1)") (class "Default")
      (node (ref "U$69") (pin "1") (pinfunction "P_1") (pintype "passive"))
    )
    (net (code "80") (name "unconnected-(U$70-P-Pad1)") (class "Default")
      (node (ref "U$70") (pin "1") (pinfunction "P_1") (pintype "passive"))
    )
    (net (code "81") (name "unconnected-(U$93-P-Pad1)") (class "Default")
      (node (ref "U$93") (pin "1") (pinfunction "P_1") (pintype "passive"))
    )
    (net (code "82") (name "unconnected-(U$94-P-Pad1)") (class "Default")
      (node (ref "U$94") (pin "1") (pinfunction "P_1") (pintype "passive"))
    )
    (net (code "83") (name "unconnected-(U$95-P-Pad1)") (class "Default")
      (node (ref "U$95") (pin "1") (pinfunction "P_1") (pintype "passive"))
    )
    (net (code "84") (name "unconnected-(U$96-P-Pad1)") (class "Default")
      (node (ref "U$96") (pin "1") (pinfunction "P_1") (pintype "passive"))
    )
    (net (code "85") (name "unconnected-(U$97-P-Pad1)") (class "Default")
      (node (ref "U$97") (pin "1") (pinfunction "P_1") (pintype "passive"))
    )
    (net (code "86") (name "unconnected-(U$98-P-Pad1)") (class "Default")
      (node (ref "U$98") (pin "1") (pinfunction "P_1") (pintype "passive"))
    )
    (net (code "87") (name "unconnected-(U$99-P-Pad1)") (class "Default")
      (node (ref "U$99") (pin "1") (pinfunction "P_1") (pintype "passive"))
    )
    (net (code "88") (name "unconnected-(U$100-P-Pad1)") (class "Default")
      (node (ref "U$100") (pin "1") (pinfunction "P_1") (pintype "passive"))
    )
    (net (code "89") (name "unconnected-(U$101-P-Pad1)") (class "Default")
      (node (ref "U$101") (pin "1") (pinfunction "P_1") (pintype "passive"))
    )
    (net (code "90") (name "unconnected-(U$102-P-Pad1)") (class "Default")
      (node (ref "U$102") (pin "1") (pinfunction "P_1") (pintype "passive"))
    )
    (net (code "91") (name "unconnected-(U$103-P-Pad1)") (class "Default")
      (node (ref "U$103") (pin "1") (pinfunction "P_1") (pintype "passive"))
    )
    (net (code "92") (name "unconnected-(U$104-P-Pad1)") (class "Default")
      (node (ref "U$104") (pin "1") (pinfunction "P_1") (pintype "passive"))
    )
    (net (code "93") (name "unconnected-(U$105-P-Pad1)") (class "Default")
      (node (ref "U$105") (pin "1") (pinfunction "P_1") (pintype "passive"))
    )
    (net (code "94") (name "unconnected-(U$106-P-Pad1)") (class "Default")
      (node (ref "U$106") (pin "1") (pinfunction "P_1") (pintype "passive"))
    )
    (net (code "95") (name "unconnected-(U$107-P-Pad1)") (class "Default")
      (node (ref "U$107") (pin "1") (pinfunction "P_1") (pintype "passive"))
    )
    (net (code "96") (name "unconnected-(U$108-P-Pad1)") (class "Default")
      (node (ref "U$108") (pin "1") (pinfunction "P_1") (pintype "passive"))
    )
    (net (code "97") (name "unconnected-(U$109-P-Pad1)") (class "Default")
      (node (ref "U$109") (pin "1") (pinfunction "P_1") (pintype "passive"))
    )
    (net (code "98") (name "unconnected-(U$110-P-Pad1)") (class "Default")
      (node (ref "U$110") (pin "1") (pinfunction "P_1") (pintype "passive"))
    )
    (net (code "99") (name "unconnected-(U$111-P-Pad1)") (class "Default")
      (node (ref "U$111") (pin "1") (pinfunction "P_1") (pintype "passive"))
    )
    (net (code "100") (name "unconnected-(U$112-P-Pad1)") (class "Default")
      (node (ref "U$112") (pin "1") (pinfunction "P_1") (pintype "passive"))
    )
    (net (code "101") (name "unconnected-(U$113-P-Pad1)") (class "Default")
      (node (ref "U$113") (pin "1") (pinfunction "P_1") (pintype "passive"))
    )
    (net (code "102") (name "unconnected-(U$114-P-Pad1)") (class "Default")
      (node (ref "U$114") (pin "1") (pinfunction "P_1") (pintype "passive"))
    )
    (net (code "103") (name "unconnected-(U$115-P-Pad1)") (class "Default")
      (node (ref "U$115") (pin "1") (pinfunction "P_1") (pintype "passive"))
    )
    (net (code "104") (name "unconnected-(U$116-P-Pad1)") (class "Default")
      (node (ref "U$116") (pin "1") (pinfunction "P_1") (pintype "passive"))
    )
    (net (code "105") (name "unconnected-(U$117-P-Pad1)") (class "Default")
      (node (ref "U$117") (pin "1") (pinfunction "P_1") (pintype "passive"))
    )
    (net (code "106") (name "unconnected-(U$118-P-Pad1)") (class "Default")
      (node (ref "U$118") (pin "1") (pinfunction "P_1") (pintype "passive"))
    )
    (net (code "107") (name "unconnected-(U$119-P-Pad1)") (class "Default")
      (node (ref "U$119") (pin "1") (pinfunction "P_1") (pintype "passive"))
    )
    (net (code "108") (name "unconnected-(U$120-P-Pad1)") (class "Default")
      (node (ref "U$120") (pin "1") (pinfunction "P_1") (pintype "passive"))
    )
    (net (code "109") (name "unconnected-(U$121-P-Pad1)") (class "Default")
      (node (ref "U$121") (pin "1") (pinfunction "P_1") (pintype "passive"))
    )
    (net (code "110") (name "unconnected-(U$122-P-Pad1)") (class "Default")
      (node (ref "U$122") (pin "1") (pinfunction "P_1") (pintype "passive"))
    )
  )
)
